# RPI_board_191219.net
KiCad netlist of a schematic drawn in EAGLE
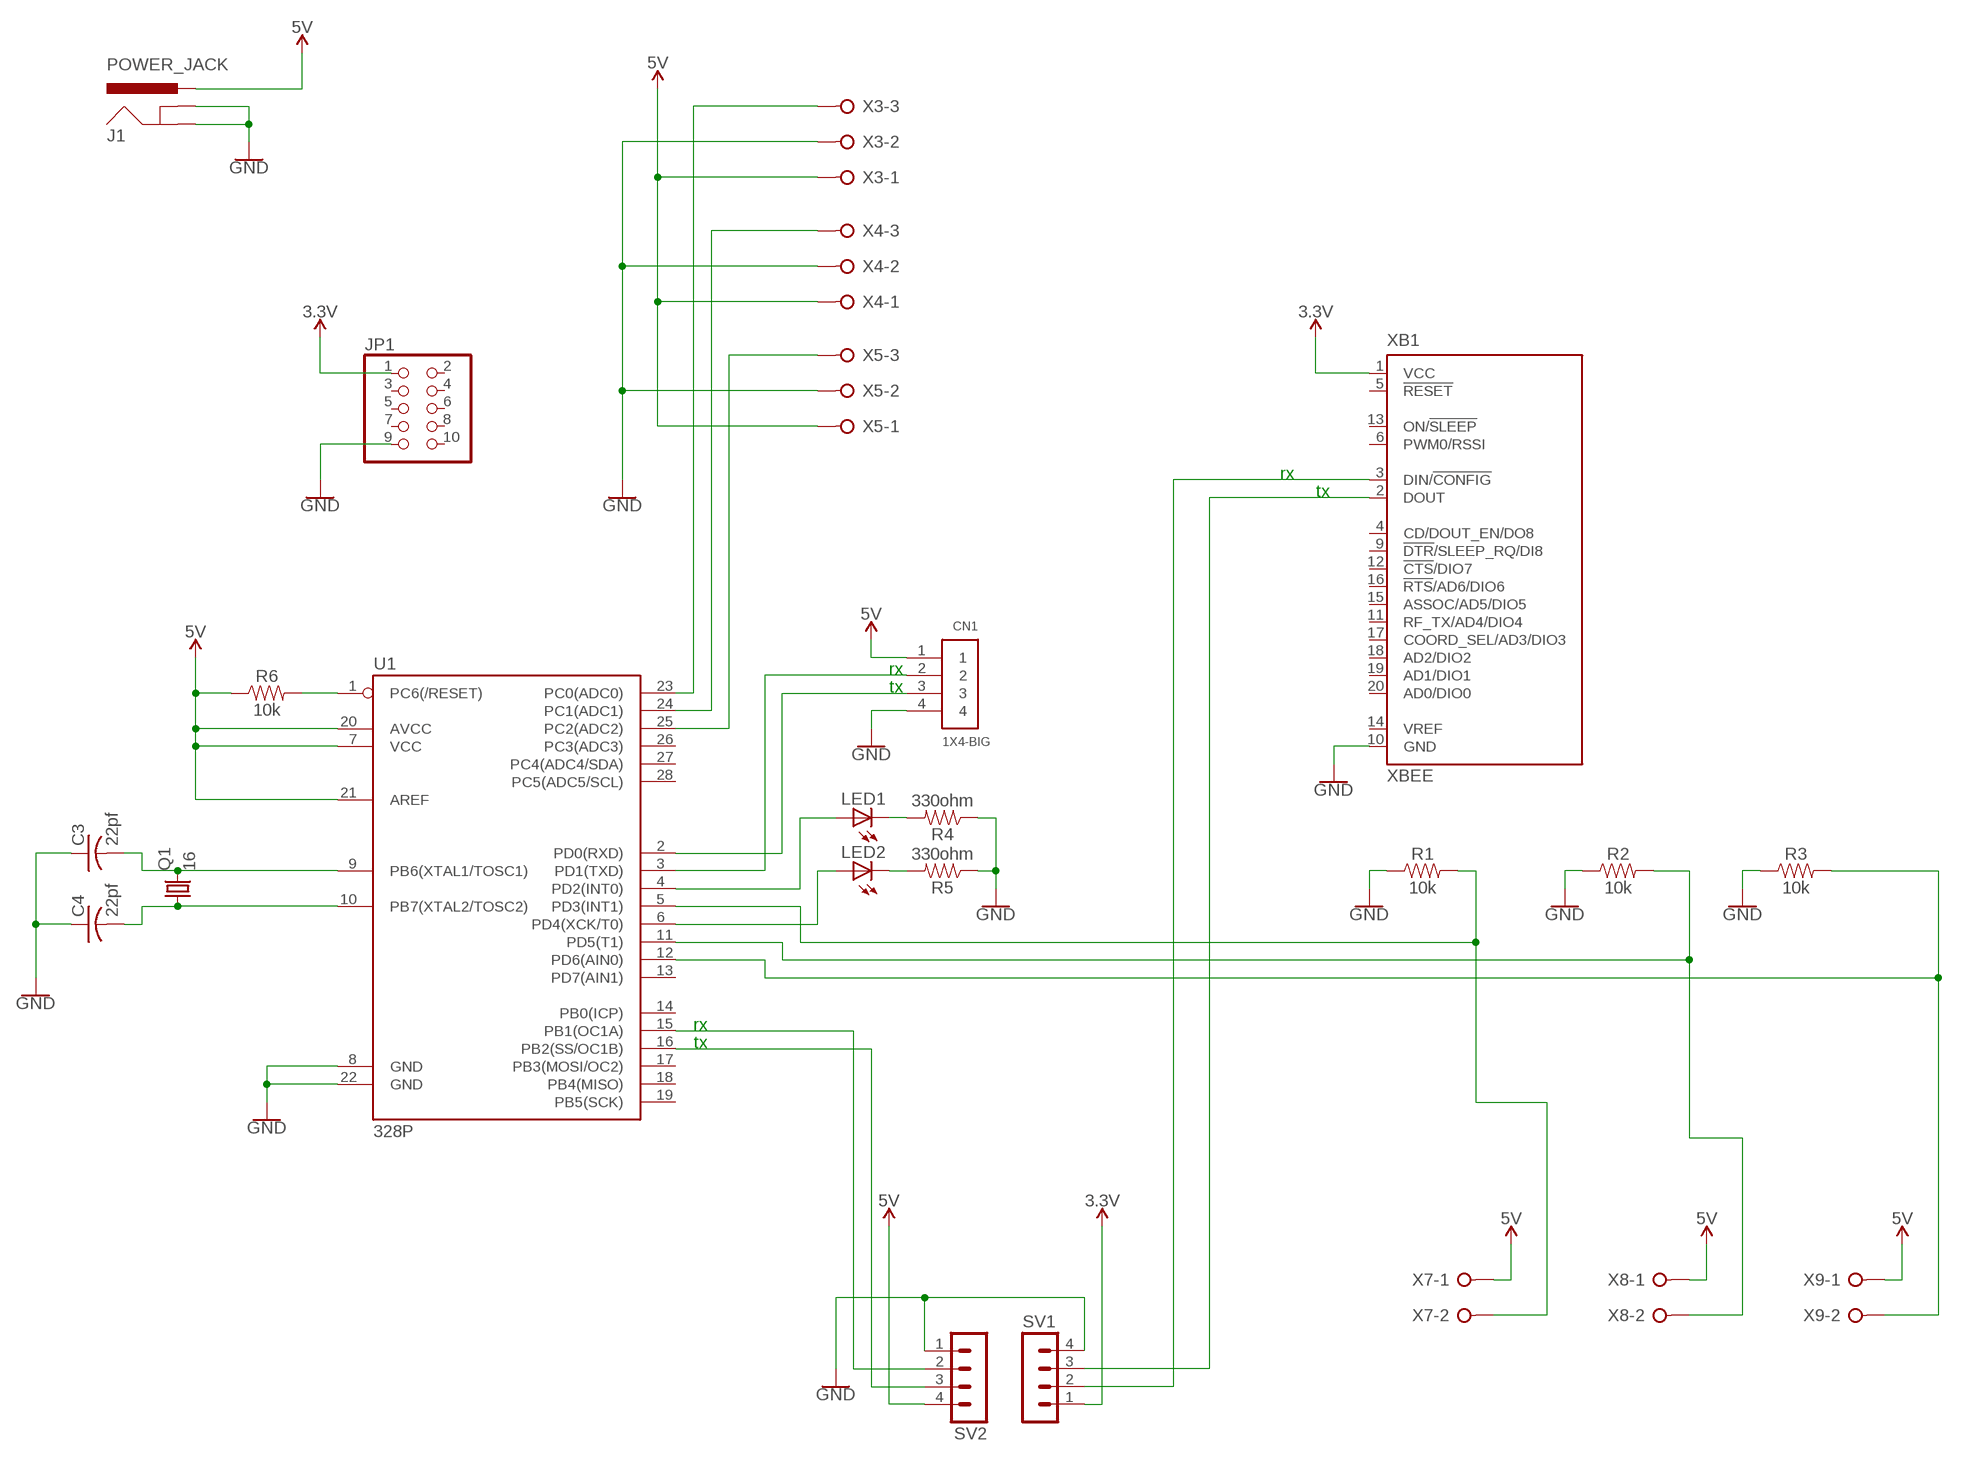
[diagram p0: schematic, sheet 1]

(export (version "E")
  (design (tool "Eeschema 10.0.6"))
  (components
    (comp (ref "C3")
      (value "22pf")
      (footprint "eagle-import:C050-025X075")
      (libsource (lib "eagle-import") (part "C-US050-025X075"))
    )
    (comp (ref "C4")
      (value "22pf")
      (footprint "eagle-import:C050-025X075")
      (libsource (lib "eagle-import") (part "C-US050-025X075"))
    )
    (comp (ref "CN1")
      (value "1X4-BIG")
      (footprint "eagle-import:1X04-BIG")
      (libsource (lib "eagle-import") (part "1X4-BIG"))
    )
    (comp (ref "J1")
      (value "POWER_JACK")
      (footprint "eagle-import:POWER_JACK_PTH")
      (libsource (lib "eagle-import") (part "POWER_JACK"))
    )
    (comp (ref "JP1")
      (value "PINHD-2X5")
      (footprint "eagle-import:2X05")
      (libsource (lib "eagle-import") (part "PINHD-2X5"))
    )
    (comp (ref "LED1")
      (value "LED3MM")
      (footprint "eagle-import:LED3MM")
      (libsource (lib "eagle-import") (part "LED3MM"))
    )
    (comp (ref "LED2")
      (value "LED3MM")
      (footprint "eagle-import:LED3MM")
      (libsource (lib "eagle-import") (part "LED3MM"))
    )
    (comp (ref "Q1")
      (value "16")
      (footprint "eagle-import:HC49_S")
      (libsource (lib "eagle-import") (part "CRYSTALHC49S"))
    )
    (comp (ref "R1")
      (value "10k")
      (footprint "eagle-import:AXIAL-0.3")
      (libsource (lib "eagle-import") (part "10KOHM-HORIZ-1/4W-5%"))
    )
    (comp (ref "R2")
      (value "10k")
      (footprint "eagle-import:AXIAL-0.3")
      (libsource (lib "eagle-import") (part "10KOHM-HORIZ-1/4W-5%"))
    )
    (comp (ref "R3")
      (value "10k")
      (footprint "eagle-import:AXIAL-0.3")
      (libsource (lib "eagle-import") (part "10KOHM-HORIZ-1/4W-5%"))
    )
    (comp (ref "R4")
      (value "330ohm")
      (footprint "eagle-import:AXIAL-0.3")
      (libsource (lib "eagle-import") (part "10KOHM-HORIZ-1/4W-5%"))
    )
    (comp (ref "R5")
      (value "330ohm")
      (footprint "eagle-import:AXIAL-0.3")
      (libsource (lib "eagle-import") (part "10KOHM-HORIZ-1/4W-5%"))
    )
    (comp (ref "R6")
      (value "10k")
      (footprint "eagle-import:AXIAL-0.3")
      (libsource (lib "eagle-import") (part "10KOHM-HORIZ-1/4W-5%"))
    )
    (comp (ref "SV1")
      (value "MA04-1")
      (footprint "eagle-import:MA04-1")
      (libsource (lib "eagle-import") (part "MA04-1"))
    )
    (comp (ref "SV2")
      (value "MA04-1")
      (footprint "eagle-import:MA04-1")
      (libsource (lib "eagle-import") (part "MA04-1"))
    )
    (comp (ref "U1")
      (value "328P")
      (footprint "eagle-import:DIP28")
      (libsource (lib "eagle-import") (part "ATMEGA328P_PDIP"))
    )
    (comp (ref "X3")
      (value "W237-3E")
      (footprint "eagle-import:W237-3E")
      (libsource (lib "eagle-import") (part "W237-3E"))
    )
    (comp (ref "X4")
      (value "W237-3E")
      (footprint "eagle-import:W237-3E")
      (libsource (lib "eagle-import") (part "W237-3E"))
    )
    (comp (ref "X5")
      (value "W237-3E")
      (footprint "eagle-import:W237-3E")
      (libsource (lib "eagle-import") (part "W237-3E"))
    )
    (comp (ref "X7")
      (value "W237-02P")
      (footprint "eagle-import:W237-132")
      (libsource (lib "eagle-import") (part "W237-02P"))
    )
    (comp (ref "X8")
      (value "W237-02P")
      (footprint "eagle-import:W237-132")
      (libsource (lib "eagle-import") (part "W237-02P"))
    )
    (comp (ref "X9")
      (value "W237-02P")
      (footprint "eagle-import:W237-132")
      (libsource (lib "eagle-import") (part "W237-02P"))
    )
    (comp (ref "XB1")
      (value "XBEE")
      (footprint "eagle-import:XBEE")
      (fields (field (name "MPN") "XBP24-Z7UIT-004"))
      (libsource (lib "eagle-import") (part "XBEE"))
    )
  )
  (nets
    (net (code "1") (name "3.3V") (class "Default")
      (node (ref "JP1") (pin "1") (pinfunction "1_1") (pintype "passive"))
      (node (ref "SV1") (pin "1") (pinfunction "1_1") (pintype "passive"))
      (node (ref "XB1") (pin "1") (pinfunction "VCC_1") (pintype "power_in"))
    )
    (net (code "2") (name "5V") (class "Default")
      (node (ref "CN1") (pin "1") (pinfunction "1_1") (pintype "bidirectional"))
      (node (ref "J1") (pin "PWR") (pinfunction "PWR_PWR") (pintype "bidirectional"))
      (node (ref "R6") (pin "P$1") (pinfunction "1_P$1") (pintype "passive"))
      (node (ref "SV2") (pin "4") (pinfunction "4_4") (pintype "passive"))
      (node (ref "U1") (pin "20") (pinfunction "AVCC_20") (pintype "bidirectional"))
      (node (ref "U1") (pin "21") (pinfunction "AREF_21") (pintype "bidirectional"))
      (node (ref "U1") (pin "7") (pinfunction "VCC_7") (pintype "bidirectional"))
      (node (ref "X3") (pin "1") (pinfunction "KL_1") (pintype "passive"))
      (node (ref "X4") (pin "1") (pinfunction "KL_1") (pintype "passive"))
      (node (ref "X5") (pin "1") (pinfunction "KL_1") (pintype "passive"))
      (node (ref "X7") (pin "1") (pinfunction "KL_1") (pintype "passive"))
      (node (ref "X8") (pin "1") (pinfunction "KL_1") (pintype "passive"))
      (node (ref "X9") (pin "1") (pinfunction "KL_1") (pintype "passive"))
    )
    (net (code "3") (name "GND") (class "Default")
      (node (ref "C3") (pin "1") (pinfunction "1_1") (pintype "passive"))
      (node (ref "C4") (pin "1") (pinfunction "1_1") (pintype "passive"))
      (node (ref "CN1") (pin "4") (pinfunction "4_4") (pintype "bidirectional"))
      (node (ref "J1") (pin "GND") (pinfunction "GND_GND") (pintype "bidirectional"))
      (node (ref "J1") (pin "GNDBREAK") (pinfunction "GNDBREAK_GNDBREAK") (pintype "bidirectional"))
      (node (ref "JP1") (pin "9") (pinfunction "9_9") (pintype "passive"))
      (node (ref "R1") (pin "P$1") (pinfunction "1_P$1") (pintype "passive"))
      (node (ref "R2") (pin "P$1") (pinfunction "1_P$1") (pintype "passive"))
      (node (ref "R3") (pin "P$1") (pinfunction "1_P$1") (pintype "passive"))
      (node (ref "R4") (pin "P$1") (pinfunction "1_P$1") (pintype "passive"))
      (node (ref "R5") (pin "P$1") (pinfunction "1_P$1") (pintype "passive"))
      (node (ref "SV1") (pin "4") (pinfunction "4_4") (pintype "passive"))
      (node (ref "SV2") (pin "1") (pinfunction "1_1") (pintype "passive"))
      (node (ref "U1") (pin "22") (pinfunction "GND_22") (pintype "bidirectional"))
      (node (ref "U1") (pin "8") (pinfunction "GND_8") (pintype "bidirectional"))
      (node (ref "X3") (pin "2") (pinfunction "KL_2") (pintype "passive"))
      (node (ref "X4") (pin "2") (pinfunction "KL_2") (pintype "passive"))
      (node (ref "X5") (pin "2") (pinfunction "KL_2") (pintype "passive"))
      (node (ref "XB1") (pin "10") (pinfunction "GND_10") (pintype "power_in"))
    )
    (net (code "4") (name "Net-(LED1-C)") (class "Default")
      (node (ref "LED1") (pin "K") (pinfunction "C_K") (pintype "passive"))
      (node (ref "R4") (pin "P$2") (pinfunction "2_P$2") (pintype "passive"))
    )
    (net (code "5") (name "Net-(LED2-C)") (class "Default")
      (node (ref "LED2") (pin "K") (pinfunction "C_K") (pintype "passive"))
      (node (ref "R5") (pin "P$2") (pinfunction "2_P$2") (pintype "passive"))
    )
    (net (code "6") (name "Net-(R1-2)") (class "Default")
      (node (ref "R1") (pin "P$2") (pinfunction "2_P$2") (pintype "passive"))
      (node (ref "U1") (pin "5") (pinfunction "PD3(INT1)_5") (pintype "bidirectional"))
      (node (ref "X7") (pin "2") (pinfunction "KL_2") (pintype "passive"))
    )
    (net (code "7") (name "Net-(R2-2)") (class "Default")
      (node (ref "R2") (pin "P$2") (pinfunction "2_P$2") (pintype "passive"))
      (node (ref "U1") (pin "11") (pinfunction "PD5(T1)_11") (pintype "bidirectional"))
      (node (ref "X8") (pin "2") (pinfunction "KL_2") (pintype "passive"))
    )
    (net (code "8") (name "Net-(R3-2)") (class "Default")
      (node (ref "R3") (pin "P$2") (pinfunction "2_P$2") (pintype "passive"))
      (node (ref "U1") (pin "12") (pinfunction "PD6(AIN0)_12") (pintype "bidirectional"))
      (node (ref "X9") (pin "2") (pinfunction "KL_2") (pintype "passive"))
    )
    (net (code "9") (name "Net-(R6-2)") (class "Default")
      (node (ref "R6") (pin "P$2") (pinfunction "2_P$2") (pintype "passive"))
      (node (ref "U1") (pin "1") (pinfunction "PC6(/RESET)_1") (pintype "bidirectional"))
    )
    (net (code "10") (name "Net-(U1-PB1(OC1A))") (class "Default")
      (node (ref "SV2") (pin "2") (pinfunction "2_2") (pintype "passive"))
      (node (ref "U1") (pin "15") (pinfunction "PB1(OC1A)_15") (pintype "bidirectional"))
    )
    (net (code "11") (name "Net-(U1-PB2(SS{slash}OC1B))") (class "Default")
      (node (ref "SV2") (pin "3") (pinfunction "3_3") (pintype "passive"))
      (node (ref "U1") (pin "16") (pinfunction "PB2(SS/OC1B)_16") (pintype "bidirectional"))
    )
    (net (code "12") (name "Net-(U1-PB6(XTAL1{slash}TOSC1))") (class "Default")
      (node (ref "C3") (pin "2") (pinfunction "2_2") (pintype "passive"))
      (node (ref "Q1") (pin "2") (pinfunction "2_2") (pintype "passive"))
      (node (ref "U1") (pin "9") (pinfunction "PB6(XTAL1/TOSC1)_9") (pintype "bidirectional"))
    )
    (net (code "13") (name "Net-(U1-PB7(XTAL2{slash}TOSC2))") (class "Default")
      (node (ref "C4") (pin "2") (pinfunction "2_2") (pintype "passive"))
      (node (ref "Q1") (pin "1") (pinfunction "1_1") (pintype "passive"))
      (node (ref "U1") (pin "10") (pinfunction "PB7(XTAL2/TOSC2)_10") (pintype "bidirectional"))
    )
    (net (code "14") (name "Net-(U1-PC0(ADC0))") (class "Default")
      (node (ref "U1") (pin "23") (pinfunction "PC0(ADC0)_23") (pintype "bidirectional"))
      (node (ref "X3") (pin "3") (pinfunction "KL_3") (pintype "passive"))
    )
    (net (code "15") (name "Net-(U1-PC1(ADC1))") (class "Default")
      (node (ref "U1") (pin "24") (pinfunction "PC1(ADC1)_24") (pintype "bidirectional"))
      (node (ref "X4") (pin "3") (pinfunction "KL_3") (pintype "passive"))
    )
    (net (code "16") (name "Net-(U1-PC2(ADC2))") (class "Default")
      (node (ref "U1") (pin "25") (pinfunction "PC2(ADC2)_25") (pintype "bidirectional"))
      (node (ref "X5") (pin "3") (pinfunction "KL_3") (pintype "passive"))
    )
    (net (code "17") (name "Net-(U1-PD0(RXD))") (class "Default")
      (node (ref "CN1") (pin "3") (pinfunction "3_3") (pintype "bidirectional"))
      (node (ref "U1") (pin "2") (pinfunction "PD0(RXD)_2") (pintype "bidirectional"))
    )
    (net (code "18") (name "Net-(U1-PD1(TXD))") (class "Default")
      (node (ref "CN1") (pin "2") (pinfunction "2_2") (pintype "bidirectional"))
      (node (ref "U1") (pin "3") (pinfunction "PD1(TXD)_3") (pintype "bidirectional"))
    )
    (net (code "19") (name "Net-(U1-PD2(INT0))") (class "Default")
      (node (ref "LED1") (pin "A") (pinfunction "A_A") (pintype "passive"))
      (node (ref "U1") (pin "4") (pinfunction "PD2(INT0)_4") (pintype "bidirectional"))
    )
    (net (code "20") (name "Net-(U1-PD4(XCK{slash}T0))") (class "Default")
      (node (ref "LED2") (pin "A") (pinfunction "A_A") (pintype "passive"))
      (node (ref "U1") (pin "6") (pinfunction "PD4(XCK/T0)_6") (pintype "bidirectional"))
    )
    (net (code "21") (name "Net-(XB1-DIN{slash}~{CONFIG})") (class "Default")
      (node (ref "SV1") (pin "2") (pinfunction "2_2") (pintype "passive"))
      (node (ref "XB1") (pin "3") (pinfunction "DIN/~{CONFIG}_3") (pintype "input"))
    )
    (net (code "22") (name "Net-(XB1-DOUT)") (class "Default")
      (node (ref "SV1") (pin "3") (pinfunction "3_3") (pintype "passive"))
      (node (ref "XB1") (pin "2") (pinfunction "DOUT_2") (pintype "output"))
    )
    (net (code "23") (name "unconnected-(JP1-Pad2)") (class "Default")
      (node (ref "JP1") (pin "2") (pinfunction "2_2") (pintype "passive"))
    )
    (net (code "24") (name "unconnected-(JP1-Pad3)") (class "Default")
      (node (ref "JP1") (pin "3") (pinfunction "3_3") (pintype "passive"))
    )
    (net (code "25") (name "unconnected-(JP1-Pad4)") (class "Default")
      (node (ref "JP1") (pin "4") (pinfunction "4_4") (pintype "passive"))
    )
    (net (code "26") (name "unconnected-(JP1-Pad5)") (class "Default")
      (node (ref "JP1") (pin "5") (pinfunction "5_5") (pintype "passive"))
    )
    (net (code "27") (name "unconnected-(JP1-Pad6)") (class "Default")
      (node (ref "JP1") (pin "6") (pinfunction "6_6") (pintype "passive"))
    )
    (net (code "28") (name "unconnected-(JP1-Pad7)") (class "Default")
      (node (ref "JP1") (pin "7") (pinfunction "7_7") (pintype "passive"))
    )
    (net (code "29") (name "unconnected-(JP1-Pad8)") (class "Default")
      (node (ref "JP1") (pin "8") (pinfunction "8_8") (pintype "passive"))
    )
    (net (code "30") (name "unconnected-(JP1-Pad10)") (class "Default")
      (node (ref "JP1") (pin "10") (pinfunction "10_10") (pintype "passive"))
    )
    (net (code "31") (name "unconnected-(U1-PB0(ICP)-Pad14)") (class "Default")
      (node (ref "U1") (pin "14") (pinfunction "PB0(ICP)_14") (pintype "bidirectional"))
    )
    (net (code "32") (name "unconnected-(U1-PB3(MOSI{slash}OC2)-Pad17)") (class "Default")
      (node (ref "U1") (pin "17") (pinfunction "PB3(MOSI/OC2)_17") (pintype "bidirectional"))
    )
    (net (code "33") (name "unconnected-(U1-PB4(MISO)-Pad18)") (class "Default")
      (node (ref "U1") (pin "18") (pinfunction "PB4(MISO)_18") (pintype "bidirectional"))
    )
    (net (code "34") (name "unconnected-(U1-PB5(SCK)-Pad19)") (class "Default")
      (node (ref "U1") (pin "19") (pinfunction "PB5(SCK)_19") (pintype "bidirectional"))
    )
    (net (code "35") (name "unconnected-(U1-PC3(ADC3)-Pad26)") (class "Default")
      (node (ref "U1") (pin "26") (pinfunction "PC3(ADC3)_26") (pintype "bidirectional"))
    )
    (net (code "36") (name "unconnected-(U1-PC4(ADC4{slash}SDA)-Pad27)") (class "Default")
      (node (ref "U1") (pin "27") (pinfunction "PC4(ADC4/SDA)_27") (pintype "bidirectional"))
    )
    (net (code "37") (name "unconnected-(U1-PC5(ADC5{slash}SCL)-Pad28)") (class "Default")
      (node (ref "U1") (pin "28") (pinfunction "PC5(ADC5/SCL)_28") (pintype "bidirectional"))
    )
    (net (code "38") (name "unconnected-(U1-PD7(AIN1)-Pad13)") (class "Default")
      (node (ref "U1") (pin "13") (pinfunction "PD7(AIN1)_13") (pintype "bidirectional"))
    )
    (net (code "39") (name "unconnected-(XB1-AD0{slash}DIO0-Pad20)") (class "Default")
      (node (ref "XB1") (pin "20") (pinfunction "AD0/DIO0_20") (pintype "bidirectional"))
    )
    (net (code "40") (name "unconnected-(XB1-AD1{slash}DIO1-Pad19)") (class "Default")
      (node (ref "XB1") (pin "19") (pinfunction "AD1/DIO1_19") (pintype "bidirectional"))
    )
    (net (code "41") (name "unconnected-(XB1-AD2{slash}DIO2-Pad18)") (class "Default")
      (node (ref "XB1") (pin "18") (pinfunction "AD2/DIO2_18") (pintype "bidirectional"))
    )
    (net (code "42") (name "unconnected-(XB1-ASSOC{slash}AD5{slash}DIO5-Pad15)") (class "Default")
      (node (ref "XB1") (pin "15") (pinfunction "ASSOC/AD5/DIO5_15") (pintype "bidirectional"))
    )
    (net (code "43") (name "unconnected-(XB1-CD{slash}DOUT_EN{slash}DO8-Pad4)") (class "Default")
      (node (ref "XB1") (pin "4") (pinfunction "CD/DOUT_EN/DO8_4") (pintype "output"))
    )
    (net (code "44") (name "unconnected-(XB1-COORD_SEL{slash}AD3{slash}DIO3-Pad17)") (class "Default")
      (node (ref "XB1") (pin "17") (pinfunction "COORD_SEL/AD3/DIO3_17") (pintype "bidirectional"))
    )
    (net (code "45") (name "unconnected-(XB1-ON{slash}~{SLEEP}-Pad13)") (class "Default")
      (node (ref "XB1") (pin "13") (pinfunction "ON/~{SLEEP}_13") (pintype "output"))
    )
    (net (code "46") (name "unconnected-(XB1-PWM0{slash}RSSI-Pad6)") (class "Default")
      (node (ref "XB1") (pin "6") (pinfunction "PWM0/RSSI_6") (pintype "output"))
    )
    (net (code "47") (name "unconnected-(XB1-RF_TX{slash}AD4{slash}DIO4-Pad11)") (class "Default")
      (node (ref "XB1") (pin "11") (pinfunction "RF_TX/AD4/DIO4_11") (pintype "bidirectional"))
    )
    (net (code "48") (name "unconnected-(XB1-VREF-Pad14)") (class "Default")
      (node (ref "XB1") (pin "14") (pinfunction "VREF_14") (pintype "input"))
    )
    (net (code "49") (name "unconnected-(XB1-~{CTS}{slash}DIO7-Pad12)") (class "Default")
      (node (ref "XB1") (pin "12") (pinfunction "~{CTS}/DIO7_12") (pintype "bidirectional"))
    )
    (net (code "50") (name "unconnected-(XB1-~{DTR}{slash}SLEEP_RQ{slash}DI8-Pad9)") (class "Default")
      (node (ref "XB1") (pin "9") (pinfunction "~{DTR}/SLEEP_RQ/DI8_9") (pintype "bidirectional"))
    )
    (net (code "51") (name "unconnected-(XB1-~{RESET}-Pad5)") (class "Default")
      (node (ref "XB1") (pin "5") (pinfunction "~{RESET}_5") (pintype "input"))
    )
    (net (code "52") (name "unconnected-(XB1-~{RTS}{slash}AD6{slash}DIO6-Pad16)") (class "Default")
      (node (ref "XB1") (pin "16") (pinfunction "~{RTS}/AD6/DIO6_16") (pintype "bidirectional"))
    )
  )
)
